# cinamin.net
KiCad netlist of a schematic drawn in EAGLE
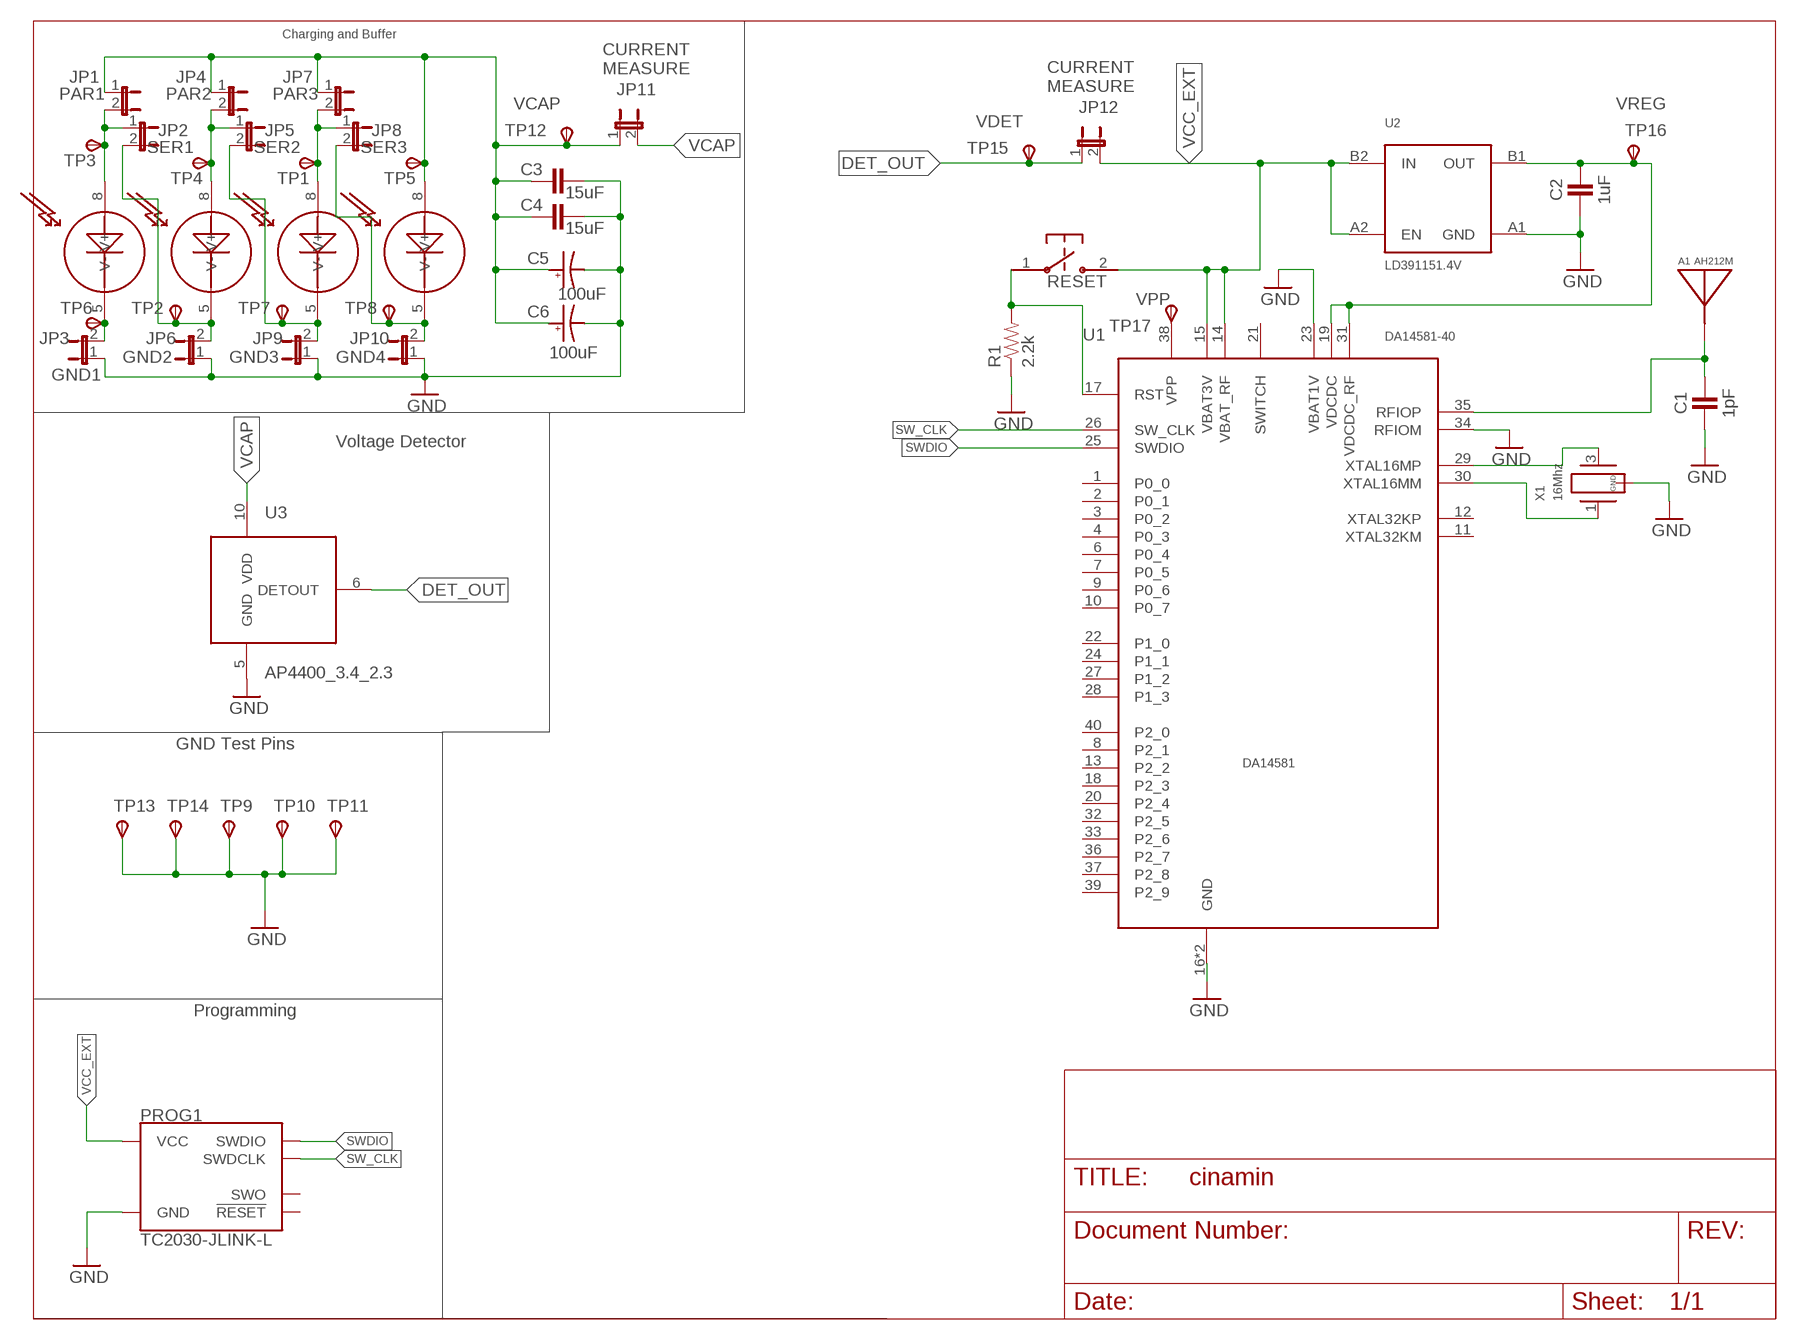
[diagram p0: schematic, sheet 1]

(export (version "E")
  (design (tool "Eeschema 10.0.6"))
  (components
    (comp (ref "A1")
      (value "AH212M")
      (footprint "eagle-import:AH212M")
      (libsource (lib "eagle-import") (part "AH212M"))
    )
    (comp (ref "C1")
      (value "1pF")
      (footprint "eagle-import:0402_CAP")
      (libsource (lib "eagle-import") (part "CAPACITOR"))
    )
    (comp (ref "C2")
      (value "1uF")
      (footprint "eagle-import:0402_CAP")
      (libsource (lib "eagle-import") (part "CAPACITOR"))
    )
    (comp (ref "C3")
      (value "15uF")
      (footprint "eagle-import:0402_CAP")
      (libsource (lib "eagle-import") (part "CAPACITOR"))
    )
    (comp (ref "C4")
      (value "15uF")
      (footprint "eagle-import:0402_CAP")
      (libsource (lib "eagle-import") (part "CAPACITOR"))
    )
    (comp (ref "C5")
      (value "100uF")
      (footprint "eagle-import:CAP0603")
      (libsource (lib "eagle-import") (part "CAP_POL0603"))
    )
    (comp (ref "C6")
      (value "100uF")
      (footprint "eagle-import:CAP0603")
      (libsource (lib "eagle-import") (part "CAP_POL0603"))
    )
    (comp (ref "D1")
      (value "CPC1822")
      (footprint "eagle-import:SOIC-8")
      (libsource (lib "eagle-import") (part "CPC1822"))
    )
    (comp (ref "D2")
      (value "CPC1822")
      (footprint "eagle-import:SOIC-8")
      (libsource (lib "eagle-import") (part "CPC1822"))
    )
    (comp (ref "D3")
      (value "CPC1822")
      (footprint "eagle-import:SOIC-8")
      (libsource (lib "eagle-import") (part "CPC1822"))
    )
    (comp (ref "D4")
      (value "CPC1822")
      (footprint "eagle-import:SOIC-8")
      (libsource (lib "eagle-import") (part "CPC1822"))
    )
    (comp (ref "JP1")
      (value "PAR1")
      (footprint "eagle-import:1X02")
      (libsource (lib "eagle-import") (part "JUMPER-2PTH"))
    )
    (comp (ref "JP2")
      (value "SER1")
      (footprint "eagle-import:1X02")
      (libsource (lib "eagle-import") (part "JUMPER-2PTH"))
    )
    (comp (ref "JP3")
      (value "GND1")
      (footprint "eagle-import:1X02")
      (libsource (lib "eagle-import") (part "JUMPER-2PTH"))
    )
    (comp (ref "JP4")
      (value "PAR2")
      (footprint "eagle-import:1X02")
      (libsource (lib "eagle-import") (part "JUMPER-2PTH"))
    )
    (comp (ref "JP5")
      (value "SER2")
      (footprint "eagle-import:1X02")
      (libsource (lib "eagle-import") (part "JUMPER-2PTH"))
    )
    (comp (ref "JP6")
      (value "GND2")
      (footprint "eagle-import:1X02")
      (libsource (lib "eagle-import") (part "JUMPER-2PTH"))
    )
    (comp (ref "JP7")
      (value "PAR3")
      (footprint "eagle-import:1X02")
      (libsource (lib "eagle-import") (part "JUMPER-2PTH"))
    )
    (comp (ref "JP8")
      (value "SER3")
      (footprint "eagle-import:1X02")
      (libsource (lib "eagle-import") (part "JUMPER-2PTH"))
    )
    (comp (ref "JP9")
      (value "GND3")
      (footprint "eagle-import:1X02")
      (libsource (lib "eagle-import") (part "JUMPER-2PTH"))
    )
    (comp (ref "JP10")
      (value "GND4")
      (footprint "eagle-import:1X02")
      (libsource (lib "eagle-import") (part "JUMPER-2PTH"))
    )
    (comp (ref "JP11")
      (value "CURRENT_MEASURE1")
      (footprint "eagle-import:1X02")
      (libsource (lib "eagle-import") (part "JUMPER-2PTH"))
    )
    (comp (ref "JP12")
      (value "CURRENT_MEASURE2")
      (footprint "eagle-import:1X02")
      (libsource (lib "eagle-import") (part "JUMPER-2PTH"))
    )
    (comp (ref "PROG1")
      (value "TC2030-JLINK-L")
      (footprint "eagle-import:TC2030-IDC")
      (libsource (lib "eagle-import") (part "TC2030-JLINK-L"))
    )
    (comp (ref "R1")
      (value "2.2k")
      (footprint "eagle-import:0402_RES")
      (libsource (lib "eagle-import") (part "RESISTOR0402_RES"))
    )
    (comp (ref "RESET")
      (value "B3U-1000P")
      (footprint "eagle-import:B3U-1000P")
      (libsource (lib "eagle-import") (part "B3U-1000P"))
    )
    (comp (ref "TP1")
      (value "D3H")
      (footprint "eagle-import:P1-13")
      (libsource (lib "eagle-import") (part "TPSPAD1-13"))
    )
    (comp (ref "TP2")
      (value "D2L")
      (footprint "eagle-import:P1-13")
      (libsource (lib "eagle-import") (part "TPSPAD1-13"))
    )
    (comp (ref "TP3")
      (value "D1H")
      (footprint "eagle-import:P1-13")
      (libsource (lib "eagle-import") (part "TPSPAD1-13"))
    )
    (comp (ref "TP4")
      (value "D2H")
      (footprint "eagle-import:P1-13")
      (libsource (lib "eagle-import") (part "TPSPAD1-13"))
    )
    (comp (ref "TP5")
      (value "D4H")
      (footprint "eagle-import:P1-13")
      (libsource (lib "eagle-import") (part "TPSPAD1-13"))
    )
    (comp (ref "TP6")
      (value "D1L")
      (footprint "eagle-import:P1-13")
      (libsource (lib "eagle-import") (part "TPSPAD1-13"))
    )
    (comp (ref "TP7")
      (value "D3L")
      (footprint "eagle-import:P1-13")
      (libsource (lib "eagle-import") (part "TPSPAD1-13"))
    )
    (comp (ref "TP8")
      (value "D4L")
      (footprint "eagle-import:P1-13")
      (libsource (lib "eagle-import") (part "TPSPAD1-13"))
    )
    (comp (ref "TP9")
      (value "GND")
      (footprint "eagle-import:P1-13")
      (libsource (lib "eagle-import") (part "TPSPAD1-13"))
    )
    (comp (ref "TP10")
      (value "GND")
      (footprint "eagle-import:P1-13")
      (libsource (lib "eagle-import") (part "TPSPAD1-13"))
    )
    (comp (ref "TP11")
      (value "GND")
      (footprint "eagle-import:P1-13")
      (libsource (lib "eagle-import") (part "TPSPAD1-13"))
    )
    (comp (ref "TP12")
      (value "VCAP")
      (footprint "eagle-import:P1-13")
      (libsource (lib "eagle-import") (part "TPSPAD1-13"))
    )
    (comp (ref "TP13")
      (value "GND")
      (footprint "eagle-import:P1-13")
      (libsource (lib "eagle-import") (part "TPSPAD1-13"))
    )
    (comp (ref "TP14")
      (value "GND")
      (footprint "eagle-import:P1-13")
      (libsource (lib "eagle-import") (part "TPSPAD1-13"))
    )
    (comp (ref "TP15")
      (value "VDET")
      (footprint "eagle-import:P1-13")
      (libsource (lib "eagle-import") (part "TPSPAD1-13"))
    )
    (comp (ref "TP16")
      (value "VREG")
      (footprint "eagle-import:P1-13")
      (libsource (lib "eagle-import") (part "TPSPAD1-13"))
    )
    (comp (ref "TP17")
      (value "VPP")
      (footprint "eagle-import:P1-13")
      (libsource (lib "eagle-import") (part "TPSPAD1-13"))
    )
    (comp (ref "U1")
      (value "DA14581-40")
      (footprint "eagle-import:QFN-40-5MM")
      (libsource (lib "eagle-import") (part "DA14581-40"))
    )
    (comp (ref "U2")
      (value "LD391151.4V")
      (footprint "eagle-import:FLIP_CHIP-4")
      (libsource (lib "eagle-import") (part "LD391151.4V"))
    )
    (comp (ref "U3")
      (value "AP4400_3.4_2.3")
      (footprint "eagle-import:TSOP-10")
      (libsource (lib "eagle-import") (part "AP4400"))
    )
    (comp (ref "X1")
      (value "16Mhz")
      (footprint "eagle-import:TXC-8Y")
      (libsource (lib "eagle-import") (part "TXC-8Y"))
    )
  )
  (nets
    (net (code "1") (name "DET_OUT") (class "Default")
      (node (ref "JP12") (pin "1") (pinfunction "1_1") (pintype "passive"))
      (node (ref "TP15") (pin "TP") (pinfunction "PP_TP") (pintype "input"))
      (node (ref "U3") (pin "6") (pinfunction "DETOUT_6") (pintype "bidirectional"))
    )
    (net (code "2") (name "GND") (class "Default")
      (node (ref "C1") (pin "2") (pinfunction "2_2") (pintype "bidirectional"))
      (node (ref "C2") (pin "2") (pinfunction "2_2") (pintype "bidirectional"))
      (node (ref "C3") (pin "2") (pinfunction "2_2") (pintype "bidirectional"))
      (node (ref "C4") (pin "2") (pinfunction "2_2") (pintype "bidirectional"))
      (node (ref "C5") (pin "NEG") (pinfunction "ANODE_NEG") (pintype "bidirectional"))
      (node (ref "C6") (pin "NEG") (pinfunction "ANODE_NEG") (pintype "bidirectional"))
      (node (ref "JP10") (pin "1") (pinfunction "1_1") (pintype "passive"))
      (node (ref "JP3") (pin "1") (pinfunction "1_1") (pintype "passive"))
      (node (ref "JP6") (pin "1") (pinfunction "1_1") (pintype "passive"))
      (node (ref "JP9") (pin "1") (pinfunction "1_1") (pintype "passive"))
      (node (ref "PROG1") (pin "5") (pinfunction "GND_5") (pintype "bidirectional"))
      (node (ref "R1") (pin "1") (pinfunction "1_1") (pintype "passive"))
      (node (ref "TP10") (pin "TP") (pinfunction "PP_TP") (pintype "input"))
      (node (ref "TP11") (pin "TP") (pinfunction "PP_TP") (pintype "input"))
      (node (ref "TP13") (pin "TP") (pinfunction "PP_TP") (pintype "input"))
      (node (ref "TP14") (pin "TP") (pinfunction "PP_TP") (pintype "input"))
      (node (ref "TP9") (pin "TP") (pinfunction "PP_TP") (pintype "input"))
      (node (ref "U1") (pin "16") (pinfunction "GND_16") (pintype "bidirectional"))
      (node (ref "U1") (pin "23") (pinfunction "VBAT1V_23") (pintype "bidirectional"))
      (node (ref "U1") (pin "34") (pinfunction "RFIOM_34") (pintype "bidirectional"))
      (node (ref "U1") (pin "PAD") (pinfunction "GND_PAD") (pintype "bidirectional"))
      (node (ref "U2") (pin "A1") (pinfunction "GND_A1") (pintype "bidirectional"))
      (node (ref "U3") (pin "5") (pinfunction "GND_5") (pintype "bidirectional"))
      (node (ref "X1") (pin "2") (pinfunction "GND_2") (pintype "bidirectional"))
      (node (ref "X1") (pin "4") (pinfunction "GND_4") (pintype "bidirectional"))
    )
    (net (code "3") (name "Net-(A1-ANTENNA)") (class "Default")
      (node (ref "A1") (pin "P1") (pinfunction "ANTENNA_P1") (pintype "bidirectional"))
      (node (ref "C1") (pin "1") (pinfunction "1_1") (pintype "bidirectional"))
      (node (ref "U1") (pin "35") (pinfunction "RFIOP_35") (pintype "bidirectional"))
    )
    (net (code "4") (name "Net-(C5-CATHODE)") (class "Default")
      (node (ref "C3") (pin "1") (pinfunction "1_1") (pintype "bidirectional"))
      (node (ref "C4") (pin "1") (pinfunction "1_1") (pintype "bidirectional"))
      (node (ref "C5") (pin "POS") (pinfunction "CATHODE_POS") (pintype "bidirectional"))
      (node (ref "C6") (pin "POS") (pinfunction "CATHODE_POS") (pintype "bidirectional"))
      (node (ref "D4") (pin "8") (pinfunction "V+_8") (pintype "bidirectional"))
      (node (ref "JP1") (pin "1") (pinfunction "1_1") (pintype "passive"))
      (node (ref "JP11") (pin "1") (pinfunction "1_1") (pintype "passive"))
      (node (ref "JP4") (pin "1") (pinfunction "1_1") (pintype "passive"))
      (node (ref "JP7") (pin "1") (pinfunction "1_1") (pintype "passive"))
      (node (ref "TP12") (pin "TP") (pinfunction "PP_TP") (pintype "input"))
      (node (ref "TP5") (pin "TP") (pinfunction "PP_TP") (pintype "input"))
    )
    (net (code "5") (name "Net-(D1-V+)") (class "Default")
      (node (ref "D1") (pin "8") (pinfunction "V+_8") (pintype "bidirectional"))
      (node (ref "JP1") (pin "2") (pinfunction "2_2") (pintype "passive"))
      (node (ref "JP2") (pin "1") (pinfunction "1_1") (pintype "passive"))
      (node (ref "TP3") (pin "TP") (pinfunction "PP_TP") (pintype "input"))
    )
    (net (code "6") (name "Net-(D1-V-)") (class "Default")
      (node (ref "D1") (pin "5") (pinfunction "V-_5") (pintype "bidirectional"))
      (node (ref "JP3") (pin "2") (pinfunction "2_2") (pintype "passive"))
      (node (ref "TP6") (pin "TP") (pinfunction "PP_TP") (pintype "input"))
    )
    (net (code "7") (name "Net-(D2-V+)") (class "Default")
      (node (ref "D2") (pin "8") (pinfunction "V+_8") (pintype "bidirectional"))
      (node (ref "JP4") (pin "2") (pinfunction "2_2") (pintype "passive"))
      (node (ref "JP5") (pin "1") (pinfunction "1_1") (pintype "passive"))
      (node (ref "TP4") (pin "TP") (pinfunction "PP_TP") (pintype "input"))
    )
    (net (code "8") (name "Net-(D2-V-)") (class "Default")
      (node (ref "D2") (pin "5") (pinfunction "V-_5") (pintype "bidirectional"))
      (node (ref "JP2") (pin "2") (pinfunction "2_2") (pintype "passive"))
      (node (ref "JP6") (pin "2") (pinfunction "2_2") (pintype "passive"))
      (node (ref "TP2") (pin "TP") (pinfunction "PP_TP") (pintype "input"))
    )
    (net (code "9") (name "Net-(D3-V+)") (class "Default")
      (node (ref "D3") (pin "8") (pinfunction "V+_8") (pintype "bidirectional"))
      (node (ref "JP7") (pin "2") (pinfunction "2_2") (pintype "passive"))
      (node (ref "JP8") (pin "1") (pinfunction "1_1") (pintype "passive"))
      (node (ref "TP1") (pin "TP") (pinfunction "PP_TP") (pintype "input"))
    )
    (net (code "10") (name "Net-(D3-V-)") (class "Default")
      (node (ref "D3") (pin "5") (pinfunction "V-_5") (pintype "bidirectional"))
      (node (ref "JP5") (pin "2") (pinfunction "2_2") (pintype "passive"))
      (node (ref "JP9") (pin "2") (pinfunction "2_2") (pintype "passive"))
      (node (ref "TP7") (pin "TP") (pinfunction "PP_TP") (pintype "input"))
    )
    (net (code "11") (name "Net-(D4-V-)") (class "Default")
      (node (ref "D4") (pin "5") (pinfunction "V-_5") (pintype "bidirectional"))
      (node (ref "JP10") (pin "2") (pinfunction "2_2") (pintype "passive"))
      (node (ref "JP8") (pin "2") (pinfunction "2_2") (pintype "passive"))
      (node (ref "TP8") (pin "TP") (pinfunction "PP_TP") (pintype "input"))
    )
    (net (code "12") (name "Net-(RESET-P$1)") (class "Default")
      (node (ref "R1") (pin "2") (pinfunction "2_2") (pintype "passive"))
      (node (ref "RESET") (pin "1") (pinfunction "P$1_1") (pintype "passive"))
      (node (ref "U1") (pin "17") (pinfunction "RST_17") (pintype "bidirectional"))
    )
    (net (code "13") (name "Net-(TP16-PP)") (class "Default")
      (node (ref "C2") (pin "1") (pinfunction "1_1") (pintype "bidirectional"))
      (node (ref "TP16") (pin "TP") (pinfunction "PP_TP") (pintype "input"))
      (node (ref "U1") (pin "19") (pinfunction "VDCDC_19") (pintype "bidirectional"))
      (node (ref "U1") (pin "31") (pinfunction "VDCDC_RF_31") (pintype "bidirectional"))
      (node (ref "U2") (pin "B1") (pinfunction "OUT_B1") (pintype "bidirectional"))
    )
    (net (code "14") (name "Net-(TP17-PP)") (class "Default")
      (node (ref "TP17") (pin "TP") (pinfunction "PP_TP") (pintype "input"))
      (node (ref "U1") (pin "38") (pinfunction "VPP_38") (pintype "bidirectional"))
    )
    (net (code "15") (name "Net-(U1-XTAL16MM)") (class "Default")
      (node (ref "U1") (pin "30") (pinfunction "XTAL16MM_30") (pintype "bidirectional"))
      (node (ref "X1") (pin "1") (pinfunction "1_1") (pintype "bidirectional"))
    )
    (net (code "16") (name "Net-(U1-XTAL16MP)") (class "Default")
      (node (ref "U1") (pin "29") (pinfunction "XTAL16MP_29") (pintype "bidirectional"))
      (node (ref "X1") (pin "3") (pinfunction "2_3") (pintype "bidirectional"))
    )
    (net (code "17") (name "SWDIO") (class "Default")
      (node (ref "PROG1") (pin "2") (pinfunction "SWDIO_2") (pintype "bidirectional"))
      (node (ref "U1") (pin "25") (pinfunction "SWDIO_25") (pintype "bidirectional"))
    )
    (net (code "18") (name "SW_CLK") (class "Default")
      (node (ref "PROG1") (pin "4") (pinfunction "SWDCLK_4") (pintype "bidirectional"))
      (node (ref "U1") (pin "26") (pinfunction "SW_CLK_26") (pintype "bidirectional"))
    )
    (net (code "19") (name "VCAP") (class "Default")
      (node (ref "JP11") (pin "2") (pinfunction "2_2") (pintype "passive"))
      (node (ref "U3") (pin "10") (pinfunction "VDD_10") (pintype "bidirectional"))
    )
    (net (code "20") (name "VCC_EXT") (class "Default")
      (node (ref "JP12") (pin "2") (pinfunction "2_2") (pintype "passive"))
      (node (ref "PROG1") (pin "1") (pinfunction "VCC_1") (pintype "bidirectional"))
      (node (ref "RESET") (pin "2") (pinfunction "P$2_2") (pintype "passive"))
      (node (ref "U1") (pin "14") (pinfunction "VBAT_RF_14") (pintype "bidirectional"))
      (node (ref "U1") (pin "15") (pinfunction "VBAT3V_15") (pintype "bidirectional"))
      (node (ref "U2") (pin "A2") (pinfunction "EN_A2") (pintype "bidirectional"))
      (node (ref "U2") (pin "B2") (pinfunction "IN_B2") (pintype "bidirectional"))
    )
    (net (code "21") (name "unconnected-(PROG1-SWO-Pad6)") (class "Default")
      (node (ref "PROG1") (pin "6") (pinfunction "SWO_6") (pintype "bidirectional"))
    )
    (net (code "22") (name "unconnected-(PROG1-~{RESET}-Pad3)") (class "Default")
      (node (ref "PROG1") (pin "3") (pinfunction "~{RESET}_3") (pintype "bidirectional"))
    )
    (net (code "23") (name "unconnected-(U1-P0_0-Pad1)") (class "Default")
      (node (ref "U1") (pin "1") (pinfunction "P0_0_1") (pintype "bidirectional"))
    )
    (net (code "24") (name "unconnected-(U1-P0_1-Pad2)") (class "Default")
      (node (ref "U1") (pin "2") (pinfunction "P0_1_2") (pintype "bidirectional"))
    )
    (net (code "25") (name "unconnected-(U1-P0_2-Pad3)") (class "Default")
      (node (ref "U1") (pin "3") (pinfunction "P0_2_3") (pintype "bidirectional"))
    )
    (net (code "26") (name "unconnected-(U1-P0_3-Pad4)") (class "Default")
      (node (ref "U1") (pin "4") (pinfunction "P0_3_4") (pintype "bidirectional"))
    )
    (net (code "27") (name "unconnected-(U1-P0_4-Pad6)") (class "Default")
      (node (ref "U1") (pin "6") (pinfunction "P0_4_6") (pintype "bidirectional"))
    )
    (net (code "28") (name "unconnected-(U1-P0_5-Pad7)") (class "Default")
      (node (ref "U1") (pin "7") (pinfunction "P0_5_7") (pintype "bidirectional"))
    )
    (net (code "29") (name "unconnected-(U1-P0_6-Pad9)") (class "Default")
      (node (ref "U1") (pin "9") (pinfunction "P0_6_9") (pintype "bidirectional"))
    )
    (net (code "30") (name "unconnected-(U1-P0_7-Pad10)") (class "Default")
      (node (ref "U1") (pin "10") (pinfunction "P0_7_10") (pintype "bidirectional"))
    )
    (net (code "31") (name "unconnected-(U1-P1_0-Pad22)") (class "Default")
      (node (ref "U1") (pin "22") (pinfunction "P1_0_22") (pintype "bidirectional"))
    )
    (net (code "32") (name "unconnected-(U1-P1_1-Pad24)") (class "Default")
      (node (ref "U1") (pin "24") (pinfunction "P1_1_24") (pintype "bidirectional"))
    )
    (net (code "33") (name "unconnected-(U1-P1_2-Pad27)") (class "Default")
      (node (ref "U1") (pin "27") (pinfunction "P1_2_27") (pintype "bidirectional"))
    )
    (net (code "34") (name "unconnected-(U1-P1_3-Pad28)") (class "Default")
      (node (ref "U1") (pin "28") (pinfunction "P1_3_28") (pintype "bidirectional"))
    )
    (net (code "35") (name "unconnected-(U1-P2_0-Pad40)") (class "Default")
      (node (ref "U1") (pin "40") (pinfunction "P2_0_40") (pintype "bidirectional"))
    )
    (net (code "36") (name "unconnected-(U1-P2_1-Pad8)") (class "Default")
      (node (ref "U1") (pin "8") (pinfunction "P2_1_8") (pintype "bidirectional"))
    )
    (net (code "37") (name "unconnected-(U1-P2_2-Pad13)") (class "Default")
      (node (ref "U1") (pin "13") (pinfunction "P2_2_13") (pintype "bidirectional"))
    )
    (net (code "38") (name "unconnected-(U1-P2_3-Pad18)") (class "Default")
      (node (ref "U1") (pin "18") (pinfunction "P2_3_18") (pintype "bidirectional"))
    )
    (net (code "39") (name "unconnected-(U1-P2_4-Pad20)") (class "Default")
      (node (ref "U1") (pin "20") (pinfunction "P2_4_20") (pintype "bidirectional"))
    )
    (net (code "40") (name "unconnected-(U1-P2_5-Pad32)") (class "Default")
      (node (ref "U1") (pin "32") (pinfunction "P2_5_32") (pintype "bidirectional"))
    )
    (net (code "41") (name "unconnected-(U1-P2_6-Pad33)") (class "Default")
      (node (ref "U1") (pin "33") (pinfunction "P2_6_33") (pintype "bidirectional"))
    )
    (net (code "42") (name "unconnected-(U1-P2_7-Pad36)") (class "Default")
      (node (ref "U1") (pin "36") (pinfunction "P2_7_36") (pintype "bidirectional"))
    )
    (net (code "43") (name "unconnected-(U1-P2_8-Pad37)") (class "Default")
      (node (ref "U1") (pin "37") (pinfunction "P2_8_37") (pintype "bidirectional"))
    )
    (net (code "44") (name "unconnected-(U1-P2_9-Pad39)") (class "Default")
      (node (ref "U1") (pin "39") (pinfunction "P2_9_39") (pintype "bidirectional"))
    )
    (net (code "45") (name "unconnected-(U1-SWITCH-Pad21)") (class "Default")
      (node (ref "U1") (pin "21") (pinfunction "SWITCH_21") (pintype "bidirectional"))
    )
    (net (code "46") (name "unconnected-(U1-XTAL32KM-Pad11)") (class "Default")
      (node (ref "U1") (pin "11") (pinfunction "XTAL32KM_11") (pintype "bidirectional"))
    )
    (net (code "47") (name "unconnected-(U1-XTAL32KP-Pad12)") (class "Default")
      (node (ref "U1") (pin "12") (pinfunction "XTAL32KP_12") (pintype "bidirectional"))
    )
  )
)
